# OBCComms.net
KiCad netlist of a schematic drawn in Altium Designer
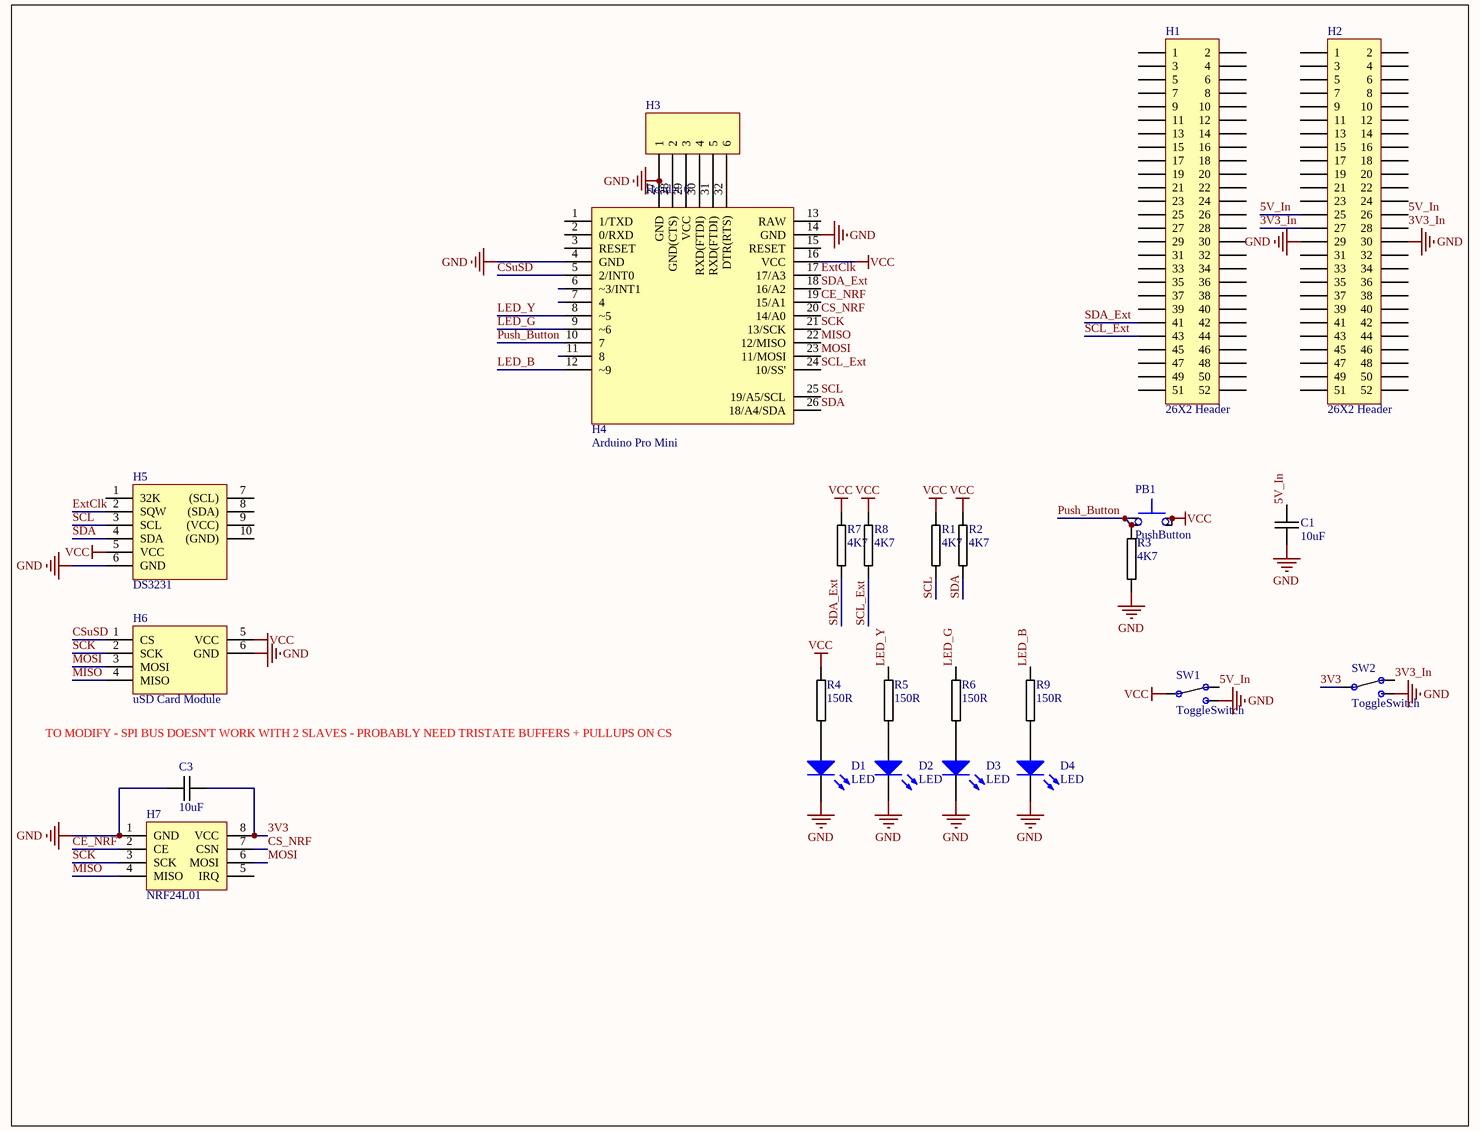
[diagram p0: OBCComms.SchDoc]

(export (version "E")
  (design (tool "Eeschema 10.0.6"))
  (components
    (comp (ref "C1")
      (value "10uF")
      (footprint "0805C-TBD")
      (description "CAPACITOR 0805 CERAMIC")
      (libsource (lib "vh_altium_library") (part "0805C-100nF-25V-X7R-MUR"))
    )
    (comp (ref "C3")
      (value "10uF")
      (footprint "0805C-GENERIC")
      (description "CAPACITOR 0805 CERAMIC")
      (fields
        (field (name "MANUFACTURER PART NUMBER") "C2012X5R1C106M")
        (field (name "MANUFACTURER") "TDK Corporation")
      )
      (libsource (lib "vh_altium_library") (part "0805C-10UF-16V-X5R-TDK"))
    )
    (comp (ref "D1")
      (value "LED")
      (footprint "LED")
      (description "Small LED")
      (libsource (lib "Components") (part "LED"))
    )
    (comp (ref "D2")
      (value "LED")
      (footprint "LED")
      (description "Small LED")
      (libsource (lib "Components") (part "LED"))
    )
    (comp (ref "D3")
      (value "LED")
      (footprint "LED")
      (description "Small LED")
      (libsource (lib "Components") (part "LED"))
    )
    (comp (ref "D4")
      (value "LED")
      (footprint "LED")
      (description "Small LED")
      (libsource (lib "Components") (part "LED"))
    )
    (comp (ref "H1")
      (value "26X2 Header")
      (footprint "26X2 Header")
      (libsource (lib "CustomParts") (part "26X2 Header"))
    )
    (comp (ref "H2")
      (value "26X2 Header")
      (footprint "26X2 Header")
      (libsource (lib "CustomParts") (part "26X2 Header"))
    )
    (comp (ref "H3")
      (value "Header 6")
      (footprint "HDR1X6")
      (description "Header, 6-Pin")
      (fields (field (name "PUBLISHER") "Altium Limited"))
      (libsource (lib "Miscellaneous Connectors") (part "Header 6"))
    )
    (comp (ref "H4")
      (value "Arduino Pro Mini")
      (footprint "Arduino Pro Mini")
      (libsource (lib "Components") (part "Arduino Pro Mini"))
    )
    (comp (ref "H5")
      (value "DS3231")
      (footprint "RTC")
      (description "RTC")
      (libsource (lib "Components") (part "DS3231"))
    )
    (comp (ref "H6")
      (value "uSD Card Module")
      (footprint "uSD Card Module")
      (libsource (lib "Components") (part "uSD Card Module"))
    )
    (comp (ref "H7")
      (value "NRF24L01")
      (footprint "NRF24L01")
      (description "Radio Transceiver")
      (libsource (lib "Components") (part "NRF24L01"))
    )
    (comp (ref "PB1")
      (value "PushButton")
      (footprint "PushButton")
      (libsource (lib "SBv1Components") (part "PushButton"))
    )
    (comp (ref "R1")
      (value "4K7")
      (footprint "0805R-4K7")
      (description "RESISTOR 0805 1/4 WATT THIN FILM")
      (libsource (lib "vh_altium_library") (part "0805R-4K7"))
    )
    (comp (ref "R2")
      (value "4K7")
      (footprint "0805R-4K7")
      (description "RESISTOR 0805 1/4 WATT THIN FILM")
      (libsource (lib "vh_altium_library") (part "0805R-4K7"))
    )
    (comp (ref "R3")
      (value "4K7")
      (footprint "0805R-4K7")
      (description "RESISTOR 0805 1/4 WATT THIN FILM")
      (libsource (lib "vh_altium_library") (part "0805R-4K7"))
    )
    (comp (ref "R4")
      (value "150R")
      (footprint "0805R-150")
      (description "RESISTOR 0805 1/4 WATT THIN FILM")
      (libsource (lib "vh_altium_library") (part "0805R-150"))
    )
    (comp (ref "R5")
      (value "150R")
      (footprint "0805R-150")
      (description "RESISTOR 0805 1/4 WATT THIN FILM")
      (libsource (lib "vh_altium_library") (part "0805R-150"))
    )
    (comp (ref "R6")
      (value "150R")
      (footprint "0805R-150")
      (description "RESISTOR 0805 1/4 WATT THIN FILM")
      (libsource (lib "vh_altium_library") (part "0805R-150"))
    )
    (comp (ref "R7")
      (value "4K7")
      (footprint "0805R-4K7")
      (description "RESISTOR 0805 1/4 WATT THIN FILM")
      (libsource (lib "vh_altium_library") (part "0805R-4K7"))
    )
    (comp (ref "R8")
      (value "4K7")
      (footprint "0805R-4K7")
      (description "RESISTOR 0805 1/4 WATT THIN FILM")
      (libsource (lib "vh_altium_library") (part "0805R-4K7"))
    )
    (comp (ref "R9")
      (value "150R")
      (footprint "0805R-150")
      (description "RESISTOR 0805 1/4 WATT THIN FILM")
      (libsource (lib "vh_altium_library") (part "0805R-150"))
    )
    (comp (ref "SW1")
      (value "ToggleSwitch")
      (footprint "SWITCHFOOTPRINT")
      (libsource (lib "SBv1Components") (part "ToggleSwitch"))
    )
    (comp (ref "SW2")
      (value "ToggleSwitch")
      (footprint "SWITCHFOOTPRINT")
      (libsource (lib "SBv1Components") (part "ToggleSwitch"))
    )
  )
  (nets
    (net (code "1") (name "/3V3") (class "Default")
      (node (ref "C3") (pin "2") (pintype "passive"))
      (node (ref "H7") (pin "8") (pinfunction "VCC_8") (pintype "passive"))
      (node (ref "SW2") (pin "23") (pinfunction "23_23") (pintype "passive"))
    )
    (net (code "2") (name "/3V3_In") (class "Default")
      (node (ref "H2") (pin "27") (pinfunction "27_27") (pintype "passive"))
      (node (ref "H2") (pin "28") (pinfunction "28_28") (pintype "passive"))
      (node (ref "SW2") (pin "24") (pinfunction "24_24") (pintype "passive"))
    )
    (net (code "3") (name "/5V_In") (class "Default")
      (node (ref "C1") (pin "1") (pintype "passive"))
      (node (ref "H2") (pin "25") (pinfunction "25_25") (pintype "passive"))
      (node (ref "H2") (pin "26") (pinfunction "26_26") (pintype "passive"))
      (node (ref "SW1") (pin "24") (pinfunction "24_24") (pintype "passive"))
    )
    (net (code "4") (name "/CE_NRF") (class "Default")
      (node (ref "H4") (pin "19") (pinfunction "15/A1_19") (pintype "passive"))
      (node (ref "H7") (pin "2") (pinfunction "CE_2") (pintype "passive"))
    )
    (net (code "5") (name "/CS_NRF") (class "Default")
      (node (ref "H4") (pin "20") (pinfunction "14/A0_20") (pintype "passive"))
      (node (ref "H7") (pin "7") (pinfunction "CSN_7") (pintype "passive"))
    )
    (net (code "6") (name "/CSuSD") (class "Default")
      (node (ref "H4") (pin "5") (pinfunction "2/INT0_5") (pintype "passive"))
      (node (ref "H6") (pin "1") (pinfunction "CS_1") (pintype "passive"))
    )
    (net (code "7") (name "/ExtClk") (class "Default")
      (node (ref "H4") (pin "17") (pinfunction "17/A3_17") (pintype "passive"))
      (node (ref "H5") (pin "2") (pinfunction "SQW_2") (pintype "passive"))
    )
    (net (code "8") (name "/LED_B") (class "Default")
      (node (ref "H4") (pin "12") (pinfunction "~9_12") (pintype "passive"))
      (node (ref "R9") (pin "1") (pintype "passive"))
    )
    (net (code "9") (name "/LED_G") (class "Default")
      (node (ref "H4") (pin "9") (pinfunction "~6_9") (pintype "passive"))
      (node (ref "R6") (pin "1") (pintype "passive"))
    )
    (net (code "10") (name "/LED_Y") (class "Default")
      (node (ref "H4") (pin "8") (pinfunction "~5_8") (pintype "passive"))
      (node (ref "R5") (pin "1") (pintype "passive"))
    )
    (net (code "11") (name "/MISO") (class "Default")
      (node (ref "H4") (pin "22") (pinfunction "12/MISO_22") (pintype "passive"))
      (node (ref "H6") (pin "4") (pinfunction "MISO_4") (pintype "passive"))
      (node (ref "H7") (pin "4") (pinfunction "MISO_4") (pintype "passive"))
    )
    (net (code "12") (name "/MOSI") (class "Default")
      (node (ref "H4") (pin "23") (pinfunction "11/MOSI_23") (pintype "passive"))
      (node (ref "H6") (pin "3") (pinfunction "MOSI_3") (pintype "passive"))
      (node (ref "H7") (pin "6") (pinfunction "MOSI_6") (pintype "passive"))
    )
    (net (code "13") (name "/Push_Button") (class "Default")
      (node (ref "H4") (pin "10") (pinfunction "7_10") (pintype "passive"))
      (node (ref "PB1") (pin "26") (pinfunction "26_26") (pintype "passive"))
      (node (ref "PB1") (pin "28") (pinfunction "28_28") (pintype "passive"))
      (node (ref "R3") (pin "1") (pintype "passive"))
    )
    (net (code "14") (name "/SCK") (class "Default")
      (node (ref "H4") (pin "21") (pinfunction "13/SCK_21") (pintype "passive"))
      (node (ref "H6") (pin "2") (pinfunction "SCK_2") (pintype "passive"))
      (node (ref "H7") (pin "3") (pinfunction "SCK_3") (pintype "passive"))
    )
    (net (code "15") (name "/SCL") (class "Default")
      (node (ref "H4") (pin "25") (pinfunction "19/A5/SCL_25") (pintype "passive"))
      (node (ref "H5") (pin "3") (pinfunction "SCL_3") (pintype "passive"))
      (node (ref "R1") (pin "2") (pintype "passive"))
    )
    (net (code "16") (name "/SCL_Ext") (class "Default")
      (node (ref "H1") (pin "43") (pinfunction "43_43") (pintype "passive"))
      (node (ref "H4") (pin "24") (pinfunction "10/SS'_24") (pintype "passive"))
      (node (ref "R8") (pin "2") (pintype "passive"))
    )
    (net (code "17") (name "/SDA") (class "Default")
      (node (ref "H4") (pin "26") (pinfunction "18/A4/SDA_26") (pintype "passive"))
      (node (ref "H5") (pin "4") (pinfunction "SDA_4") (pintype "passive"))
      (node (ref "R2") (pin "2") (pintype "passive"))
    )
    (net (code "18") (name "/SDA_Ext") (class "Default")
      (node (ref "H1") (pin "41") (pinfunction "41_41") (pintype "passive"))
      (node (ref "H4") (pin "18") (pinfunction "16/A2_18") (pintype "passive"))
      (node (ref "R7") (pin "2") (pintype "passive"))
    )
    (net (code "19") (name "GND") (class "Default")
      (node (ref "C1") (pin "2") (pintype "passive"))
      (node (ref "C3") (pin "1") (pintype "passive"))
      (node (ref "D1") (pin "2") (pinfunction "K_2") (pintype "passive"))
      (node (ref "D2") (pin "2") (pinfunction "K_2") (pintype "passive"))
      (node (ref "D3") (pin "2") (pinfunction "K_2") (pintype "passive"))
      (node (ref "D4") (pin "2") (pinfunction "K_2") (pintype "passive"))
      (node (ref "H2") (pin "29") (pinfunction "29_29") (pintype "passive"))
      (node (ref "H2") (pin "30") (pinfunction "30_30") (pintype "passive"))
      (node (ref "H3") (pin "1") (pinfunction "1_1") (pintype "passive"))
      (node (ref "H4") (pin "14") (pinfunction "GND_14") (pintype "passive"))
      (node (ref "H4") (pin "27") (pinfunction "GND_27") (pintype "passive"))
      (node (ref "H4") (pin "4") (pinfunction "GND_4") (pintype "passive"))
      (node (ref "H5") (pin "6") (pinfunction "GND_6") (pintype "passive"))
      (node (ref "H6") (pin "6") (pinfunction "GND_6") (pintype "passive"))
      (node (ref "H7") (pin "1") (pinfunction "GND_1") (pintype "passive"))
      (node (ref "R3") (pin "2") (pintype "passive"))
      (node (ref "SW1") (pin "25") (pinfunction "25_25") (pintype "passive"))
      (node (ref "SW2") (pin "25") (pinfunction "25_25") (pintype "passive"))
    )
    (net (code "20") (name "Net-(D1-A)") (class "Default")
      (node (ref "D1") (pin "1") (pinfunction "A_1") (pintype "passive"))
      (node (ref "R4") (pin "2") (pintype "passive"))
    )
    (net (code "21") (name "Net-(D2-A)") (class "Default")
      (node (ref "D2") (pin "1") (pinfunction "A_1") (pintype "passive"))
      (node (ref "R5") (pin "2") (pintype "passive"))
    )
    (net (code "22") (name "Net-(D3-A)") (class "Default")
      (node (ref "D3") (pin "1") (pinfunction "A_1") (pintype "passive"))
      (node (ref "R6") (pin "2") (pintype "passive"))
    )
    (net (code "23") (name "Net-(D4-A)") (class "Default")
      (node (ref "D4") (pin "1") (pinfunction "A_1") (pintype "passive"))
      (node (ref "R9") (pin "2") (pintype "passive"))
    )
    (net (code "24") (name "Net-(H3-Pad3)") (class "Default")
      (node (ref "H3") (pin "3") (pinfunction "3_3") (pintype "passive"))
      (node (ref "H4") (pin "29") (pinfunction "VCC_29") (pintype "passive"))
    )
    (net (code "25") (name "Net-(H3-Pad4)") (class "Default")
      (node (ref "H3") (pin "4") (pinfunction "4_4") (pintype "passive"))
      (node (ref "H4") (pin "30") (pinfunction "RXD(FTDI)_30") (pintype "passive"))
    )
    (net (code "26") (name "Net-(H3-Pad5)") (class "Default")
      (node (ref "H3") (pin "5") (pinfunction "5_5") (pintype "passive"))
      (node (ref "H4") (pin "31") (pinfunction "RXD(FTDI)_31") (pintype "passive"))
    )
    (net (code "27") (name "Net-(H4-DTR(RTS))") (class "Default")
      (node (ref "H3") (pin "6") (pinfunction "6_6") (pintype "passive"))
      (node (ref "H4") (pin "32") (pinfunction "DTR(RTS)_32") (pintype "passive"))
    )
    (net (code "28") (name "Net-(H4-GND(CTS))") (class "Default")
      (node (ref "H3") (pin "2") (pinfunction "2_2") (pintype "passive"))
      (node (ref "H4") (pin "28") (pinfunction "GND(CTS)_28") (pintype "passive"))
    )
    (net (code "29") (name "VCC") (class "Default")
      (node (ref "H4") (pin "16") (pinfunction "VCC_16") (pintype "passive"))
      (node (ref "H5") (pin "5") (pinfunction "VCC_5") (pintype "passive"))
      (node (ref "H6") (pin "5") (pinfunction "VCC_5") (pintype "passive"))
      (node (ref "PB1") (pin "27") (pinfunction "27_27") (pintype "passive"))
      (node (ref "PB1") (pin "29") (pinfunction "29_29") (pintype "passive"))
      (node (ref "R1") (pin "1") (pintype "passive"))
      (node (ref "R2") (pin "1") (pintype "passive"))
      (node (ref "R4") (pin "1") (pintype "passive"))
      (node (ref "R7") (pin "1") (pintype "passive"))
      (node (ref "R8") (pin "1") (pintype "passive"))
      (node (ref "SW1") (pin "23") (pinfunction "23_23") (pintype "passive"))
    )
    (net (code "30") (name "unconnected-(H1-Pad1)") (class "Default")
      (node (ref "H1") (pin "1") (pinfunction "1_1") (pintype "passive"))
    )
    (net (code "31") (name "unconnected-(H1-Pad2)") (class "Default")
      (node (ref "H1") (pin "2") (pinfunction "2_2") (pintype "passive"))
    )
    (net (code "32") (name "unconnected-(H1-Pad3)") (class "Default")
      (node (ref "H1") (pin "3") (pinfunction "3_3") (pintype "passive"))
    )
    (net (code "33") (name "unconnected-(H1-Pad4)") (class "Default")
      (node (ref "H1") (pin "4") (pinfunction "4_4") (pintype "passive"))
    )
    (net (code "34") (name "unconnected-(H1-Pad5)") (class "Default")
      (node (ref "H1") (pin "5") (pinfunction "5_5") (pintype "passive"))
    )
    (net (code "35") (name "unconnected-(H1-Pad6)") (class "Default")
      (node (ref "H1") (pin "6") (pinfunction "6_6") (pintype "passive"))
    )
    (net (code "36") (name "unconnected-(H1-Pad7)") (class "Default")
      (node (ref "H1") (pin "7") (pinfunction "7_7") (pintype "passive"))
    )
    (net (code "37") (name "unconnected-(H1-Pad8)") (class "Default")
      (node (ref "H1") (pin "8") (pinfunction "8_8") (pintype "passive"))
    )
    (net (code "38") (name "unconnected-(H1-Pad9)") (class "Default")
      (node (ref "H1") (pin "9") (pinfunction "9_9") (pintype "passive"))
    )
    (net (code "39") (name "unconnected-(H1-Pad10)") (class "Default")
      (node (ref "H1") (pin "10") (pinfunction "10_10") (pintype "passive"))
    )
    (net (code "40") (name "unconnected-(H1-Pad11)") (class "Default")
      (node (ref "H1") (pin "11") (pinfunction "11_11") (pintype "passive"))
    )
    (net (code "41") (name "unconnected-(H1-Pad12)") (class "Default")
      (node (ref "H1") (pin "12") (pinfunction "12_12") (pintype "passive"))
    )
    (net (code "42") (name "unconnected-(H1-Pad13)") (class "Default")
      (node (ref "H1") (pin "13") (pinfunction "13_13") (pintype "passive"))
    )
    (net (code "43") (name "unconnected-(H1-Pad14)") (class "Default")
      (node (ref "H1") (pin "14") (pinfunction "14_14") (pintype "passive"))
    )
    (net (code "44") (name "unconnected-(H1-Pad15)") (class "Default")
      (node (ref "H1") (pin "15") (pinfunction "15_15") (pintype "passive"))
    )
    (net (code "45") (name "unconnected-(H1-Pad16)") (class "Default")
      (node (ref "H1") (pin "16") (pinfunction "16_16") (pintype "passive"))
    )
    (net (code "46") (name "unconnected-(H1-Pad17)") (class "Default")
      (node (ref "H1") (pin "17") (pinfunction "17_17") (pintype "passive"))
    )
    (net (code "47") (name "unconnected-(H1-Pad18)") (class "Default")
      (node (ref "H1") (pin "18") (pinfunction "18_18") (pintype "passive"))
    )
    (net (code "48") (name "unconnected-(H1-Pad19)") (class "Default")
      (node (ref "H1") (pin "19") (pinfunction "19_19") (pintype "passive"))
    )
    (net (code "49") (name "unconnected-(H1-Pad20)") (class "Default")
      (node (ref "H1") (pin "20") (pinfunction "20_20") (pintype "passive"))
    )
    (net (code "50") (name "unconnected-(H1-Pad21)") (class "Default")
      (node (ref "H1") (pin "21") (pinfunction "21_21") (pintype "passive"))
    )
    (net (code "51") (name "unconnected-(H1-Pad22)") (class "Default")
      (node (ref "H1") (pin "22") (pinfunction "22_22") (pintype "passive"))
    )
    (net (code "52") (name "unconnected-(H1-Pad23)") (class "Default")
      (node (ref "H1") (pin "23") (pinfunction "23_23") (pintype "passive"))
    )
    (net (code "53") (name "unconnected-(H1-Pad24)") (class "Default")
      (node (ref "H1") (pin "24") (pinfunction "24_24") (pintype "passive"))
    )
    (net (code "54") (name "unconnected-(H1-Pad25)") (class "Default")
      (node (ref "H1") (pin "25") (pinfunction "25_25") (pintype "passive"))
    )
    (net (code "55") (name "unconnected-(H1-Pad26)") (class "Default")
      (node (ref "H1") (pin "26") (pinfunction "26_26") (pintype "passive"))
    )
    (net (code "56") (name "unconnected-(H1-Pad27)") (class "Default")
      (node (ref "H1") (pin "27") (pinfunction "27_27") (pintype "passive"))
    )
    (net (code "57") (name "unconnected-(H1-Pad28)") (class "Default")
      (node (ref "H1") (pin "28") (pinfunction "28_28") (pintype "passive"))
    )
    (net (code "58") (name "unconnected-(H1-Pad29)") (class "Default")
      (node (ref "H1") (pin "29") (pinfunction "29_29") (pintype "passive"))
    )
    (net (code "59") (name "unconnected-(H1-Pad30)") (class "Default")
      (node (ref "H1") (pin "30") (pinfunction "30_30") (pintype "passive"))
    )
    (net (code "60") (name "unconnected-(H1-Pad31)") (class "Default")
      (node (ref "H1") (pin "31") (pinfunction "31_31") (pintype "passive"))
    )
    (net (code "61") (name "unconnected-(H1-Pad32)") (class "Default")
      (node (ref "H1") (pin "32") (pinfunction "32_32") (pintype "passive"))
    )
    (net (code "62") (name "unconnected-(H1-Pad33)") (class "Default")
      (node (ref "H1") (pin "33") (pinfunction "33_33") (pintype "passive"))
    )
    (net (code "63") (name "unconnected-(H1-Pad34)") (class "Default")
      (node (ref "H1") (pin "34") (pinfunction "34_34") (pintype "passive"))
    )
    (net (code "64") (name "unconnected-(H1-Pad35)") (class "Default")
      (node (ref "H1") (pin "35") (pinfunction "35_35") (pintype "passive"))
    )
    (net (code "65") (name "unconnected-(H1-Pad36)") (class "Default")
      (node (ref "H1") (pin "36") (pinfunction "36_36") (pintype "passive"))
    )
    (net (code "66") (name "unconnected-(H1-Pad37)") (class "Default")
      (node (ref "H1") (pin "37") (pinfunction "37_37") (pintype "passive"))
    )
    (net (code "67") (name "unconnected-(H1-Pad38)") (class "Default")
      (node (ref "H1") (pin "38") (pinfunction "38_38") (pintype "passive"))
    )
    (net (code "68") (name "unconnected-(H1-Pad39)") (class "Default")
      (node (ref "H1") (pin "39") (pinfunction "39_39") (pintype "passive"))
    )
    (net (code "69") (name "unconnected-(H1-Pad40)") (class "Default")
      (node (ref "H1") (pin "40") (pinfunction "40_40") (pintype "passive"))
    )
    (net (code "70") (name "unconnected-(H1-Pad42)") (class "Default")
      (node (ref "H1") (pin "42") (pinfunction "42_42") (pintype "passive"))
    )
    (net (code "71") (name "unconnected-(H1-Pad44)") (class "Default")
      (node (ref "H1") (pin "44") (pinfunction "44_44") (pintype "passive"))
    )
    (net (code "72") (name "unconnected-(H1-Pad45)") (class "Default")
      (node (ref "H1") (pin "45") (pinfunction "45_45") (pintype "passive"))
    )
    (net (code "73") (name "unconnected-(H1-Pad46)") (class "Default")
      (node (ref "H1") (pin "46") (pinfunction "46_46") (pintype "passive"))
    )
    (net (code "74") (name "unconnected-(H1-Pad47)") (class "Default")
      (node (ref "H1") (pin "47") (pinfunction "47_47") (pintype "passive"))
    )
    (net (code "75") (name "unconnected-(H1-Pad48)") (class "Default")
      (node (ref "H1") (pin "48") (pinfunction "48_48") (pintype "passive"))
    )
    (net (code "76") (name "unconnected-(H1-Pad49)") (class "Default")
      (node (ref "H1") (pin "49") (pinfunction "49_49") (pintype "passive"))
    )
    (net (code "77") (name "unconnected-(H1-Pad50)") (class "Default")
      (node (ref "H1") (pin "50") (pinfunction "50_50") (pintype "passive"))
    )
    (net (code "78") (name "unconnected-(H1-Pad51)") (class "Default")
      (node (ref "H1") (pin "51") (pinfunction "51_51") (pintype "passive"))
    )
    (net (code "79") (name "unconnected-(H1-Pad52)") (class "Default")
      (node (ref "H1") (pin "52") (pinfunction "52_52") (pintype "passive"))
    )
    (net (code "80") (name "unconnected-(H2-Pad1)") (class "Default")
      (node (ref "H2") (pin "1") (pinfunction "1_1") (pintype "passive"))
    )
    (net (code "81") (name "unconnected-(H2-Pad2)") (class "Default")
      (node (ref "H2") (pin "2") (pinfunction "2_2") (pintype "passive"))
    )
    (net (code "82") (name "unconnected-(H2-Pad3)") (class "Default")
      (node (ref "H2") (pin "3") (pinfunction "3_3") (pintype "passive"))
    )
    (net (code "83") (name "unconnected-(H2-Pad4)") (class "Default")
      (node (ref "H2") (pin "4") (pinfunction "4_4") (pintype "passive"))
    )
    (net (code "84") (name "unconnected-(H2-Pad5)") (class "Default")
      (node (ref "H2") (pin "5") (pinfunction "5_5") (pintype "passive"))
    )
    (net (code "85") (name "unconnected-(H2-Pad6)") (class "Default")
      (node (ref "H2") (pin "6") (pinfunction "6_6") (pintype "passive"))
    )
    (net (code "86") (name "unconnected-(H2-Pad7)") (class "Default")
      (node (ref "H2") (pin "7") (pinfunction "7_7") (pintype "passive"))
    )
    (net (code "87") (name "unconnected-(H2-Pad8)") (class "Default")
      (node (ref "H2") (pin "8") (pinfunction "8_8") (pintype "passive"))
    )
    (net (code "88") (name "unconnected-(H2-Pad9)") (class "Default")
      (node (ref "H2") (pin "9") (pinfunction "9_9") (pintype "passive"))
    )
    (net (code "89") (name "unconnected-(H2-Pad10)") (class "Default")
      (node (ref "H2") (pin "10") (pinfunction "10_10") (pintype "passive"))
    )
    (net (code "90") (name "unconnected-(H2-Pad11)") (class "Default")
      (node (ref "H2") (pin "11") (pinfunction "11_11") (pintype "passive"))
    )
    (net (code "91") (name "unconnected-(H2-Pad12)") (class "Default")
      (node (ref "H2") (pin "12") (pinfunction "12_12") (pintype "passive"))
    )
    (net (code "92") (name "unconnected-(H2-Pad13)") (class "Default")
      (node (ref "H2") (pin "13") (pinfunction "13_13") (pintype "passive"))
    )
    (net (code "93") (name "unconnected-(H2-Pad14)") (class "Default")
      (node (ref "H2") (pin "14") (pinfunction "14_14") (pintype "passive"))
    )
    (net (code "94") (name "unconnected-(H2-Pad15)") (class "Default")
      (node (ref "H2") (pin "15") (pinfunction "15_15") (pintype "passive"))
    )
    (net (code "95") (name "unconnected-(H2-Pad16)") (class "Default")
      (node (ref "H2") (pin "16") (pinfunction "16_16") (pintype "passive"))
    )
    (net (code "96") (name "unconnected-(H2-Pad17)") (class "Default")
      (node (ref "H2") (pin "17") (pinfunction "17_17") (pintype "passive"))
    )
    (net (code "97") (name "unconnected-(H2-Pad18)") (class "Default")
      (node (ref "H2") (pin "18") (pinfunction "18_18") (pintype "passive"))
    )
    (net (code "98") (name "unconnected-(H2-Pad19)") (class "Default")
      (node (ref "H2") (pin "19") (pinfunction "19_19") (pintype "passive"))
    )
    (net (code "99") (name "unconnected-(H2-Pad20)") (class "Default")
      (node (ref "H2") (pin "20") (pinfunction "20_20") (pintype "passive"))
    )
    (net (code "100") (name "unconnected-(H2-Pad21)") (class "Default")
      (node (ref "H2") (pin "21") (pinfunction "21_21") (pintype "passive"))
    )
    (net (code "101") (name "unconnected-(H2-Pad22)") (class "Default")
      (node (ref "H2") (pin "22") (pinfunction "22_22") (pintype "passive"))
    )
    (net (code "102") (name "unconnected-(H2-Pad23)") (class "Default")
      (node (ref "H2") (pin "23") (pinfunction "23_23") (pintype "passive"))
    )
    (net (code "103") (name "unconnected-(H2-Pad24)") (class "Default")
      (node (ref "H2") (pin "24") (pinfunction "24_24") (pintype "passive"))
    )
    (net (code "104") (name "unconnected-(H2-Pad31)") (class "Default")
      (node (ref "H2") (pin "31") (pinfunction "31_31") (pintype "passive"))
    )
    (net (code "105") (name "unconnected-(H2-Pad32)") (class "Default")
      (node (ref "H2") (pin "32") (pinfunction "32_32") (pintype "passive"))
    )
    (net (code "106") (name "unconnected-(H2-Pad33)") (class "Default")
      (node (ref "H2") (pin "33") (pinfunction "33_33") (pintype "passive"))
    )
    (net (code "107") (name "unconnected-(H2-Pad34)") (class "Default")
      (node (ref "H2") (pin "34") (pinfunction "34_34") (pintype "passive"))
    )
    (net (code "108") (name "unconnected-(H2-Pad35)") (class "Default")
      (node (ref "H2") (pin "35") (pinfunction "35_35") (pintype "passive"))
    )
    (net (code "109") (name "unconnected-(H2-Pad36)") (class "Default")
      (node (ref "H2") (pin "36") (pinfunction "36_36") (pintype "passive"))
    )
    (net (code "110") (name "unconnected-(H2-Pad37)") (class "Default")
      (node (ref "H2") (pin "37") (pinfunction "37_37") (pintype "passive"))
    )
    (net (code "111") (name "unconnected-(H2-Pad38)") (class "Default")
      (node (ref "H2") (pin "38") (pinfunction "38_38") (pintype "passive"))
    )
    (net (code "112") (name "unconnected-(H2-Pad39)") (class "Default")
      (node (ref "H2") (pin "39") (pinfunction "39_39") (pintype "passive"))
    )
    (net (code "113") (name "unconnected-(H2-Pad40)") (class "Default")
      (node (ref "H2") (pin "40") (pinfunction "40_40") (pintype "passive"))
    )
    (net (code "114") (name "unconnected-(H2-Pad41)") (class "Default")
      (node (ref "H2") (pin "41") (pinfunction "41_41") (pintype "passive"))
    )
    (net (code "115") (name "unconnected-(H2-Pad42)") (class "Default")
      (node (ref "H2") (pin "42") (pinfunction "42_42") (pintype "passive"))
    )
    (net (code "116") (name "unconnected-(H2-Pad43)") (class "Default")
      (node (ref "H2") (pin "43") (pinfunction "43_43") (pintype "passive"))
    )
    (net (code "117") (name "unconnected-(H2-Pad44)") (class "Default")
      (node (ref "H2") (pin "44") (pinfunction "44_44") (pintype "passive"))
    )
    (net (code "118") (name "unconnected-(H2-Pad45)") (class "Default")
      (node (ref "H2") (pin "45") (pinfunction "45_45") (pintype "passive"))
    )
    (net (code "119") (name "unconnected-(H2-Pad46)") (class "Default")
      (node (ref "H2") (pin "46") (pinfunction "46_46") (pintype "passive"))
    )
    (net (code "120") (name "unconnected-(H2-Pad47)") (class "Default")
      (node (ref "H2") (pin "47") (pinfunction "47_47") (pintype "passive"))
    )
    (net (code "121") (name "unconnected-(H2-Pad48)") (class "Default")
      (node (ref "H2") (pin "48") (pinfunction "48_48") (pintype "passive"))
    )
    (net (code "122") (name "unconnected-(H2-Pad49)") (class "Default")
      (node (ref "H2") (pin "49") (pinfunction "49_49") (pintype "passive"))
    )
    (net (code "123") (name "unconnected-(H2-Pad50)") (class "Default")
      (node (ref "H2") (pin "50") (pinfunction "50_50") (pintype "passive"))
    )
    (net (code "124") (name "unconnected-(H2-Pad51)") (class "Default")
      (node (ref "H2") (pin "51") (pinfunction "51_51") (pintype "passive"))
    )
    (net (code "125") (name "unconnected-(H2-Pad52)") (class "Default")
      (node (ref "H2") (pin "52") (pinfunction "52_52") (pintype "passive"))
    )
    (net (code "126") (name "unconnected-(H4-0{slash}RXD-Pad2)") (class "Default")
      (node (ref "H4") (pin "2") (pinfunction "0/RXD_2") (pintype "passive"))
    )
    (net (code "127") (name "unconnected-(H4-1{slash}TXD-Pad1)") (class "Default")
      (node (ref "H4") (pin "1") (pinfunction "1/TXD_1") (pintype "passive"))
    )
    (net (code "128") (name "unconnected-(H4-4-Pad7)") (class "Default")
      (node (ref "H4") (pin "7") (pinfunction "4_7") (pintype "passive"))
    )
    (net (code "129") (name "unconnected-(H4-8-Pad11)") (class "Default")
      (node (ref "H4") (pin "11") (pinfunction "8_11") (pintype "passive"))
    )
    (net (code "130") (name "unconnected-(H4-RAW-Pad13)") (class "Default")
      (node (ref "H4") (pin "13") (pinfunction "RAW_13") (pintype "passive"))
    )
    (net (code "131") (name "unconnected-(H4-RESET-Pad3)") (class "Default")
      (node (ref "H4") (pin "3") (pinfunction "RESET_3") (pintype "passive"))
    )
    (net (code "132") (name "unconnected-(H4-RESET-Pad15)") (class "Default")
      (node (ref "H4") (pin "15") (pinfunction "RESET_15") (pintype "passive"))
    )
    (net (code "133") (name "unconnected-(H4-~3{slash}INT1-Pad6)") (class "Default")
      (node (ref "H4") (pin "6") (pinfunction "~3/INT1_6") (pintype "passive"))
    )
    (net (code "134") (name "unconnected-(H5-(GND)-Pad10)") (class "Default")
      (node (ref "H5") (pin "10") (pinfunction "(GND)_10") (pintype "passive"))
    )
    (net (code "135") (name "unconnected-(H5-(SCL)-Pad7)") (class "Default")
      (node (ref "H5") (pin "7") (pinfunction "(SCL)_7") (pintype "passive"))
    )
    (net (code "136") (name "unconnected-(H5-(SDA)-Pad8)") (class "Default")
      (node (ref "H5") (pin "8") (pinfunction "(SDA)_8") (pintype "passive"))
    )
    (net (code "137") (name "unconnected-(H5-(VCC)-Pad9)") (class "Default")
      (node (ref "H5") (pin "9") (pinfunction "(VCC)_9") (pintype "passive"))
    )
    (net (code "138") (name "unconnected-(H5-32K-Pad1)") (class "Default")
      (node (ref "H5") (pin "1") (pinfunction "32K_1") (pintype "passive"))
    )
    (net (code "139") (name "unconnected-(H7-IRQ-Pad5)") (class "Default")
      (node (ref "H7") (pin "5") (pinfunction "IRQ_5") (pintype "passive"))
    )
  )
)
